# os20_newenc1.net
KiCad netlist of a schematic drawn in EAGLE
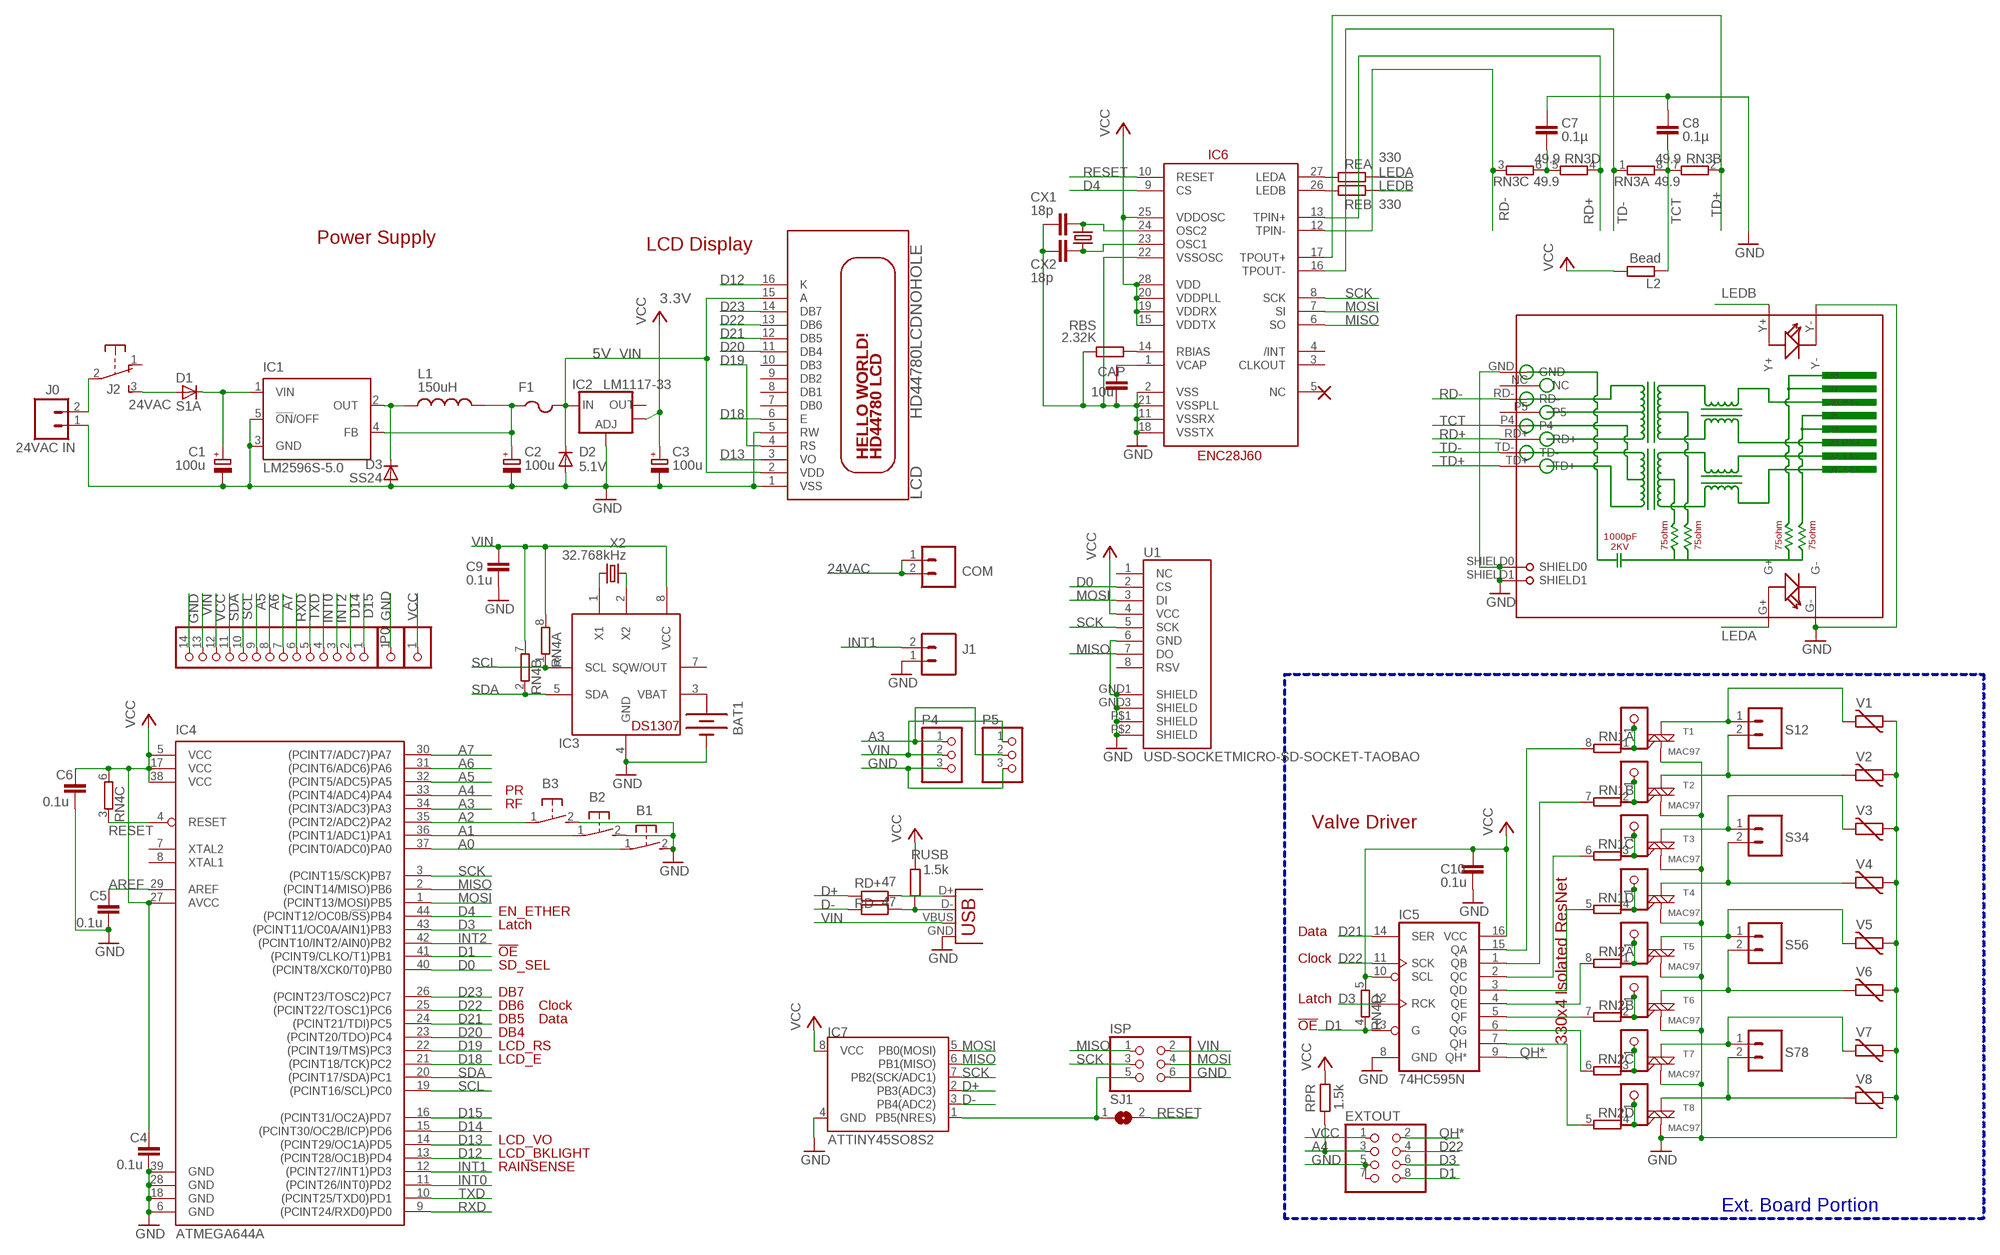
[diagram p0: schematic, sheet 1]

(export (version "E")
  (design (tool "Eeschema 10.0.6"))
  (components
    (comp (ref "B1")
      (value "31-XX")
      (footprint "eagle-import:B3F-31XX")
      (libsource (lib "eagle-import") (part "31-XX"))
    )
    (comp (ref "B2")
      (value "31-XX")
      (footprint "eagle-import:B3F-31XX")
      (libsource (lib "eagle-import") (part "31-XX"))
    )
    (comp (ref "B3")
      (value "31-XX")
      (footprint "eagle-import:B3F-31XX")
      (libsource (lib "eagle-import") (part "31-XX"))
    )
    (comp (ref "BAT1")
      (value "BATTERYBATTERY_12MM_SMT")
      (footprint "eagle-import:BATTCON_12MM_SMT")
      (libsource (lib "eagle-import") (part "BATTERYBATTERY_12MM_SMT"))
    )
    (comp (ref "C1")
      (value "100u")
      (footprint "eagle-import:E3,5-8")
      (libsource (lib "eagle-import") (part "CPOL-EUE3.5-8"))
    )
    (comp (ref "C2")
      (value "100u")
      (footprint "eagle-import:PANASONIC_D")
      (libsource (lib "eagle-import") (part "CPOL-EUD"))
    )
    (comp (ref "C3")
      (value "100u")
      (footprint "eagle-import:PANASONIC_D")
      (libsource (lib "eagle-import") (part "CPOL-EUD"))
    )
    (comp (ref "C4")
      (value "0.1u")
      (footprint "eagle-import:C0805")
      (libsource (lib "eagle-import") (part "C-EUC0805"))
    )
    (comp (ref "C5")
      (value "0.1u")
      (footprint "eagle-import:C0805")
      (libsource (lib "eagle-import") (part "C-EUC0805"))
    )
    (comp (ref "C6")
      (value "0.1u")
      (footprint "eagle-import:C0805")
      (libsource (lib "eagle-import") (part "C-EUC0805"))
    )
    (comp (ref "C7")
      (value "0.1µ")
      (footprint "eagle-import:C0805")
      (libsource (lib "eagle-import") (part "resistor_C-EUC0805"))
    )
    (comp (ref "C8")
      (value "0.1µ")
      (footprint "eagle-import:C0805")
      (libsource (lib "eagle-import") (part "resistor_C-EUC0805"))
    )
    (comp (ref "C9")
      (value "0.1u")
      (footprint "eagle-import:C0805")
      (libsource (lib "eagle-import") (part "C-EUC0805"))
    )
    (comp (ref "C10")
      (value "0.1u")
      (footprint "eagle-import:C0805")
      (libsource (lib "eagle-import") (part "C-EUC0805"))
    )
    (comp (ref "CAP")
      (value "10u")
      (footprint "eagle-import:C0805")
      (libsource (lib "eagle-import") (part "resistor_C-EUC0805"))
    )
    (comp (ref "COM")
      (value "M025MM")
      (footprint "eagle-import:SCREWTERMINAL-5MM-2")
      (libsource (lib "eagle-import") (part "M025MM"))
    )
    (comp (ref "CX1")
      (value "18p")
      (footprint "eagle-import:C0805")
      (libsource (lib "eagle-import") (part "resistor_C-EUC0805"))
    )
    (comp (ref "CX2")
      (value "18p")
      (footprint "eagle-import:C0805")
      (libsource (lib "eagle-import") (part "resistor_C-EUC0805"))
    )
    (comp (ref "D1")
      (value "S1A")
      (footprint "eagle-import:DO-214AC")
      (libsource (lib "eagle-import") (part "DIODE-DO-214AC"))
    )
    (comp (ref "D2")
      (value "5.1V")
      (footprint "eagle-import:MINIMELF")
      (libsource (lib "eagle-import") (part "DIODE-MINIMELF"))
    )
    (comp (ref "D3")
      (value "SS24")
      (footprint "eagle-import:DO-214AC")
      (libsource (lib "eagle-import") (part "DIODE-DO-214AC"))
    )
    (comp (ref "EXTOUT")
      (value "PINHD-2X4")
      (footprint "eagle-import:2X04")
      (libsource (lib "eagle-import") (part "PINHD-2X4"))
    )
    (comp (ref "F1")
      (value "PTCFUSE-1812")
      (footprint "eagle-import:1812")
      (libsource (lib "eagle-import") (part "PTCFUSE-1812"))
    )
    (comp (ref "IC1")
      (value "LM2596S-5.0")
      (footprint "eagle-import:TO263-5")
      (fields (field (name "MF") "NATIONAL SEMICONDUCTOR") (field (name "MPN") "LM2596S-ADJ/NOPB"))
      (libsource (lib "eagle-import") (part "LM2596S"))
    )
    (comp (ref "IC2")
      (value "LM1117-33")
      (footprint "eagle-import:SOT223")
      (libsource (lib "eagle-import") (part "V_REG_LM1117SOT223"))
    )
    (comp (ref "IC3")
      (value "DS1307")
      (footprint "eagle-import:SO08")
      (libsource (lib "eagle-import") (part "DS1307SOIC"))
    )
    (comp (ref "IC4")
      (value "ATMEGA644A")
      (footprint "eagle-import:TQFP44")
      (fields (field (name "MPN") "ATMEGA644PV-10AU"))
      (libsource (lib "eagle-import") (part "ATMEGA644A"))
    )
    (comp (ref "IC5")
      (value "74HC595N")
      (footprint "eagle-import:SO16")
      (libsource (lib "eagle-import") (part "74595DLS"))
    )
    (comp (ref "IC6")
      (value "ENC28J60")
      (footprint "eagle-import:SOIC28WLONG")
      (libsource (lib "eagle-import") (part "ENC28J60SO28LONG"))
    )
    (comp (ref "IC7")
      (value "ATTINY45SO8S2")
      (footprint "eagle-import:SO8S2")
      (libsource (lib "eagle-import") (part "ATTINY45SO8S2"))
    )
    (comp (ref "ISP")
      (value "PINHD-2X3")
      (footprint "eagle-import:2X03")
      (libsource (lib "eagle-import") (part "PINHD-2X3"))
    )
    (comp (ref "J0")
      (value "24VAC IN")
      (footprint "eagle-import:SCREWTERMINAL-5MM-2")
      (libsource (lib "eagle-import") (part "M025MM"))
    )
    (comp (ref "J1")
      (value "M025MM")
      (footprint "eagle-import:SCREWTERMINAL-5MM-2")
      (libsource (lib "eagle-import") (part "M025MM"))
    )
    (comp (ref "J2")
      (value "EG1206")
      (footprint "eagle-import:EG1206")
      (libsource (lib "eagle-import") (part "EG1206"))
    )
    (comp (ref "JP2")
      (value "PINHD-1X1CB")
      (footprint "eagle-import:1X01-CLEANBIG")
      (libsource (lib "eagle-import") (part "PINHD-1X1CB"))
    )
    (comp (ref "JP3")
      (value "PINHD-1X1CB")
      (footprint "eagle-import:1X01-CLEANBIG")
      (libsource (lib "eagle-import") (part "PINHD-1X1CB"))
    )
    (comp (ref "JP4")
      (value "PINHD-1X1CB")
      (footprint "eagle-import:1X01-CLEANBIG")
      (libsource (lib "eagle-import") (part "PINHD-1X1CB"))
    )
    (comp (ref "JP5")
      (value "PINHD-1X1CB")
      (footprint "eagle-import:1X01-CLEANBIG")
      (libsource (lib "eagle-import") (part "PINHD-1X1CB"))
    )
    (comp (ref "JP6")
      (value "PINHD-1X1CB")
      (footprint "eagle-import:1X01-CLEANBIG")
      (libsource (lib "eagle-import") (part "PINHD-1X1CB"))
    )
    (comp (ref "JP7")
      (value "PINHD-1X1CB")
      (footprint "eagle-import:1X01-CLEANBIG")
      (libsource (lib "eagle-import") (part "PINHD-1X1CB"))
    )
    (comp (ref "JP8")
      (value "PINHD-1X1CB")
      (footprint "eagle-import:1X01-CLEANBIG")
      (libsource (lib "eagle-import") (part "PINHD-1X1CB"))
    )
    (comp (ref "JP9")
      (value "PINHD-1X1CB")
      (footprint "eagle-import:1X01-CLEANBIG")
      (libsource (lib "eagle-import") (part "PINHD-1X1CB"))
    )
    (comp (ref "L1")
      (value "150uH")
      (footprint "eagle-import:CDRH125")
      (libsource (lib "eagle-import") (part "INDUCTORPWR"))
    )
    (comp (ref "L2")
      (value "Bead")
      (footprint "eagle-import:R0805")
      (libsource (lib "eagle-import") (part "R-EU_R0805"))
    )
    (comp (ref "LCD")
      (value "HD44780LCDNOHOLE")
      (footprint "eagle-import:LCD1602A")
      (libsource (lib "eagle-import") (part "HD44780LCDNOHOLE"))
    )
    (comp (ref "P0")
      (value "PINHD-1X14-CB")
      (footprint "eagle-import:1X14-CB")
      (libsource (lib "eagle-import") (part "PINHD-1X14-CB"))
    )
    (comp (ref "P1")
      (value "PINHD-1X1CB")
      (footprint "eagle-import:1X01-CLEANBIG")
      (libsource (lib "eagle-import") (part "PINHD-1X1CB"))
    )
    (comp (ref "P2")
      (value "PINHD-1X1CB")
      (footprint "eagle-import:1X01-CLEANBIG")
      (libsource (lib "eagle-import") (part "PINHD-1X1CB"))
    )
    (comp (ref "P4")
      (value "PINHD-1X3")
      (footprint "eagle-import:1X03")
      (libsource (lib "eagle-import") (part "PINHD-1X3"))
    )
    (comp (ref "P5")
      (value "PINHD-1X3")
      (footprint "eagle-import:1X03")
      (libsource (lib "eagle-import") (part "PINHD-1X3"))
    )
    (comp (ref "RBS")
      (value "2.32K")
      (footprint "eagle-import:R0805")
      (libsource (lib "eagle-import") (part "R-EU_R0805"))
    )
    (comp (ref "RD+")
      (value "47")
      (footprint "eagle-import:R0805")
      (libsource (lib "eagle-import") (part "R-EU_R0805"))
    )
    (comp (ref "RD-")
      (value "47")
      (footprint "eagle-import:R0805")
      (libsource (lib "eagle-import") (part "R-EU_R0805"))
    )
    (comp (ref "REA")
      (value "330")
      (footprint "eagle-import:R0805")
      (libsource (lib "eagle-import") (part "R-EU_R0805"))
    )
    (comp (ref "REB")
      (value "330")
      (footprint "eagle-import:R0805")
      (libsource (lib "eagle-import") (part "R-EU_R0805"))
    )
    (comp (ref "RJ45")
      (value "HR911105A")
      (footprint "eagle-import:HR911105A")
      (libsource (lib "eagle-import") (part "HR911105A"))
    )
    (comp (ref "RN1")
      (value "4R-NEXB38V")
      (footprint "eagle-import:EXB38V")
      (libsource (lib "eagle-import") (part "4R-NEXB38V"))
    )
    (comp (ref "RN2")
      (value "4R-NEXB38V")
      (footprint "eagle-import:EXB38V")
      (libsource (lib "eagle-import") (part "4R-NEXB38V"))
    )
    (comp (ref "RN3")
      (value "49.9")
      (footprint "eagle-import:EXB38V")
      (libsource (lib "eagle-import") (part "4R-NEXB38V"))
    )
    (comp (ref "RN4")
      (value "4R-NEXB38V")
      (footprint "eagle-import:EXB38V")
      (libsource (lib "eagle-import") (part "4R-NEXB38V"))
    )
    (comp (ref "RPR")
      (value "1.5k")
      (footprint "eagle-import:R0805")
      (libsource (lib "eagle-import") (part "R-EU_R0805"))
    )
    (comp (ref "RUSB")
      (value "1.5k")
      (footprint "eagle-import:R0805")
      (libsource (lib "eagle-import") (part "R-EU_R0805"))
    )
    (comp (ref "S12")
      (value "M025MM")
      (footprint "eagle-import:SCREWTERMINAL-5MM-2")
      (libsource (lib "eagle-import") (part "M025MM"))
    )
    (comp (ref "S34")
      (value "M025MM")
      (footprint "eagle-import:SCREWTERMINAL-5MM-2")
      (libsource (lib "eagle-import") (part "M025MM"))
    )
    (comp (ref "S56")
      (value "M025MM")
      (footprint "eagle-import:SCREWTERMINAL-5MM-2")
      (libsource (lib "eagle-import") (part "M025MM"))
    )
    (comp (ref "S78")
      (value "M025MM")
      (footprint "eagle-import:SCREWTERMINAL-5MM-2")
      (libsource (lib "eagle-import") (part "M025MM"))
    )
    (comp (ref "SJ1") (value "SJ") (footprint "eagle-import:SJ") (libsource (lib "eagle-import") (part "SJ")))
    (comp (ref "T1")
      (value "MAC97")
      (footprint "eagle-import:SOT223")
      (libsource (lib "eagle-import") (part "MAC97SOT223"))
    )
    (comp (ref "T2")
      (value "MAC97")
      (footprint "eagle-import:SOT223")
      (libsource (lib "eagle-import") (part "MAC97SOT223"))
    )
    (comp (ref "T3")
      (value "MAC97")
      (footprint "eagle-import:SOT223")
      (libsource (lib "eagle-import") (part "MAC97SOT223"))
    )
    (comp (ref "T4")
      (value "MAC97")
      (footprint "eagle-import:SOT223")
      (libsource (lib "eagle-import") (part "MAC97SOT223"))
    )
    (comp (ref "T5")
      (value "MAC97")
      (footprint "eagle-import:SOT223")
      (libsource (lib "eagle-import") (part "MAC97SOT223"))
    )
    (comp (ref "T6")
      (value "MAC97")
      (footprint "eagle-import:SOT223")
      (libsource (lib "eagle-import") (part "MAC97SOT223"))
    )
    (comp (ref "T7")
      (value "MAC97")
      (footprint "eagle-import:SOT223")
      (libsource (lib "eagle-import") (part "MAC97SOT223"))
    )
    (comp (ref "T8")
      (value "MAC97")
      (footprint "eagle-import:SOT223")
      (libsource (lib "eagle-import") (part "MAC97SOT223"))
    )
    (comp (ref "U1")
      (value "USD-SOCKETMICRO-SD-SOCKET-TAOBAO")
      (footprint "eagle-import:MICRO-SD-SOCKET-TAOBAO")
      (libsource (lib "eagle-import") (part "USD-SOCKETMICRO-SD-SOCKET-TAOBAO"))
    )
    (comp (ref "USB")
      (value "USBPTH")
      (footprint "eagle-import:USB-B-PTH")
      (libsource (lib "eagle-import") (part "USBPTH"))
    )
    (comp (ref "V1")
      (value "MOV")
      (footprint "eagle-import:R-5")
      (libsource (lib "eagle-import") (part "VARISTOR-5"))
    )
    (comp (ref "V2")
      (value "MOV")
      (footprint "eagle-import:R-5")
      (libsource (lib "eagle-import") (part "VARISTOR-5"))
    )
    (comp (ref "V3")
      (value "MOV")
      (footprint "eagle-import:R-5")
      (libsource (lib "eagle-import") (part "VARISTOR-5"))
    )
    (comp (ref "V4")
      (value "MOV")
      (footprint "eagle-import:R-5")
      (libsource (lib "eagle-import") (part "VARISTOR-5"))
    )
    (comp (ref "V5")
      (value "MOV")
      (footprint "eagle-import:R-5")
      (libsource (lib "eagle-import") (part "VARISTOR-5"))
    )
    (comp (ref "V6")
      (value "MOV")
      (footprint "eagle-import:R-5")
      (libsource (lib "eagle-import") (part "VARISTOR-5"))
    )
    (comp (ref "V7")
      (value "MOV")
      (footprint "eagle-import:R-5")
      (libsource (lib "eagle-import") (part "VARISTOR-5"))
    )
    (comp (ref "V8")
      (value "MOV")
      (footprint "eagle-import:R-5")
      (libsource (lib "eagle-import") (part "VARISTOR-5"))
    )
    (comp (ref "X1")
      (value "25MHz")
      (footprint "eagle-import:HC49US")
      (libsource (lib "eagle-import") (part "CRYSTALHC49US"))
    )
    (comp (ref "X2")
      (value "32.768kHz")
      (footprint "eagle-import:TC26H")
      (libsource (lib "eagle-import") (part "crystal_CRYSTALTC26H"))
    )
  )
  (nets
    (net (code "1") (name "/24VAC") (class "Default")
      (node (ref "COM") (pin "1") (pinfunction "1_1") (pintype "passive"))
      (node (ref "COM") (pin "2") (pinfunction "2_2") (pintype "passive"))
      (node (ref "D1") (pin "A") (pinfunction "A_A") (pintype "passive"))
      (node (ref "J2") (pin "3") (pinfunction "S_3") (pintype "passive"))
    )
    (net (code "2") (name "/A0") (class "Default")
      (node (ref "B1") (pin "1") (pinfunction "P_1") (pintype "passive"))
      (node (ref "IC4") (pin "37") (pinfunction "(PCINT0/ADC0)PA0_37") (pintype "bidirectional"))
    )
    (net (code "3") (name "/A1") (class "Default")
      (node (ref "B2") (pin "1") (pinfunction "P_1") (pintype "passive"))
      (node (ref "IC4") (pin "36") (pinfunction "(PCINT1/ADC1)PA1_36") (pintype "bidirectional"))
    )
    (net (code "4") (name "/A2") (class "Default")
      (node (ref "B3") (pin "1") (pinfunction "P_1") (pintype "passive"))
      (node (ref "IC4") (pin "35") (pinfunction "(PCINT2/ADC2)PA2_35") (pintype "bidirectional"))
    )
    (net (code "5") (name "/A3") (class "Default")
      (node (ref "IC4") (pin "34") (pinfunction "(PCINT3/ADC3)PA3_34") (pintype "bidirectional"))
      (node (ref "P4") (pin "1") (pinfunction "1_1") (pintype "passive"))
      (node (ref "P5") (pin "2") (pinfunction "2_2") (pintype "passive"))
    )
    (net (code "6") (name "/A4") (class "Default")
      (node (ref "EXTOUT") (pin "3") (pinfunction "3_3") (pintype "passive"))
      (node (ref "IC4") (pin "33") (pinfunction "(PCINT4/ADC4)PA4_33") (pintype "bidirectional"))
      (node (ref "RPR") (pin "1") (pinfunction "1_1") (pintype "passive"))
    )
    (net (code "7") (name "/A5") (class "Default")
      (node (ref "IC4") (pin "32") (pinfunction "(PCINT5/ADC5)PA5_32") (pintype "bidirectional"))
      (node (ref "P0") (pin "9") (pinfunction "9_9") (pintype "passive"))
    )
    (net (code "8") (name "/A6") (class "Default")
      (node (ref "IC4") (pin "31") (pinfunction "(PCINT6/ADC6)PA6_31") (pintype "bidirectional"))
      (node (ref "P0") (pin "8") (pinfunction "8_8") (pintype "passive"))
    )
    (net (code "9") (name "/A7") (class "Default")
      (node (ref "IC4") (pin "30") (pinfunction "(PCINT7/ADC7)PA7_30") (pintype "bidirectional"))
      (node (ref "P0") (pin "7") (pinfunction "7_7") (pintype "passive"))
    )
    (net (code "10") (name "/AREF") (class "Default")
      (node (ref "C5") (pin "1") (pinfunction "1_1") (pintype "passive"))
      (node (ref "IC4") (pin "29") (pinfunction "AREF_29") (pintype "passive"))
    )
    (net (code "11") (name "/D+") (class "Default")
      (node (ref "IC7") (pin "2") (pinfunction "PB3(ADC3)_2") (pintype "bidirectional"))
      (node (ref "RD+") (pin "1") (pinfunction "1_1") (pintype "passive"))
    )
    (net (code "12") (name "/D-") (class "Default")
      (node (ref "IC7") (pin "3") (pinfunction "PB4(ADC2)_3") (pintype "bidirectional"))
      (node (ref "RD-") (pin "1") (pinfunction "1_1") (pintype "passive"))
    )
    (net (code "13") (name "/D0") (class "Default")
      (node (ref "IC4") (pin "40") (pinfunction "(PCINT8/XCK0/T0)PB0_40") (pintype "bidirectional"))
      (node (ref "U1") (pin "2") (pinfunction "CS_2") (pintype "bidirectional"))
    )
    (net (code "14") (name "/D1") (class "Default")
      (node (ref "EXTOUT") (pin "8") (pinfunction "8_8") (pintype "passive"))
      (node (ref "IC4") (pin "41") (pinfunction "(PCINT9/CLKO/T1)PB1_41") (pintype "bidirectional"))
      (node (ref "IC5") (pin "13") (pinfunction "G_13") (pintype "input"))
      (node (ref "RN4") (pin "4") (pinfunction "1_4") (pintype "passive"))
    )
    (net (code "15") (name "/D3") (class "Default")
      (node (ref "EXTOUT") (pin "6") (pinfunction "6_6") (pintype "passive"))
      (node (ref "IC4") (pin "43") (pinfunction "(PCINT11/OC0A/AIN1)PB3_43") (pintype "bidirectional"))
      (node (ref "IC5") (pin "12") (pinfunction "RCK_12") (pintype "input"))
    )
    (net (code "16") (name "/D4") (class "Default")
      (node (ref "IC4") (pin "44") (pinfunction "(PCINT12/OC0B/~{SS})PB4_44") (pintype "bidirectional"))
      (node (ref "IC6") (pin "9") (pinfunction "CS_9") (pintype "bidirectional"))
    )
    (net (code "17") (name "/D12") (class "Default")
      (node (ref "IC4") (pin "13") (pinfunction "(PCINT28/OC1B)PD4_13") (pintype "bidirectional"))
      (node (ref "LCD") (pin "16") (pinfunction "K_16") (pintype "input"))
    )
    (net (code "18") (name "/D13") (class "Default")
      (node (ref "IC4") (pin "14") (pinfunction "(PCINT29/OC1A)PD5_14") (pintype "bidirectional"))
      (node (ref "LCD") (pin "3") (pinfunction "VO_3") (pintype "input"))
    )
    (net (code "19") (name "/D14") (class "Default")
      (node (ref "IC4") (pin "15") (pinfunction "(PCINT30/OC2B/ICP)PD6_15") (pintype "bidirectional"))
      (node (ref "P0") (pin "2") (pinfunction "2_2") (pintype "passive"))
    )
    (net (code "20") (name "/D15") (class "Default")
      (node (ref "IC4") (pin "16") (pinfunction "(PCINT31/OC2A)PD7_16") (pintype "bidirectional"))
      (node (ref "P0") (pin "1") (pinfunction "1_1") (pintype "passive"))
    )
    (net (code "21") (name "/D18") (class "Default")
      (node (ref "IC4") (pin "21") (pinfunction "(PCINT18/TCK)PC2_21") (pintype "output"))
      (node (ref "LCD") (pin "6") (pinfunction "E_6") (pintype "input"))
    )
    (net (code "22") (name "/D19") (class "Default")
      (node (ref "IC4") (pin "22") (pinfunction "(PCINT19/TMS)PC3_22") (pintype "output"))
      (node (ref "LCD") (pin "4") (pinfunction "RS_4") (pintype "input"))
    )
    (net (code "23") (name "/D20") (class "Default")
      (node (ref "IC4") (pin "23") (pinfunction "(PCINT20/TDO)PC4_23") (pintype "output"))
      (node (ref "LCD") (pin "11") (pinfunction "DB4_11") (pintype "bidirectional"))
    )
    (net (code "24") (name "/D21") (class "Default")
      (node (ref "IC4") (pin "24") (pinfunction "(PCINT21/TDI)PC5_24") (pintype "output"))
      (node (ref "IC5") (pin "14") (pinfunction "SER_14") (pintype "input"))
      (node (ref "LCD") (pin "12") (pinfunction "DB5_12") (pintype "bidirectional"))
    )
    (net (code "25") (name "/D22") (class "Default")
      (node (ref "EXTOUT") (pin "4") (pinfunction "4_4") (pintype "passive"))
      (node (ref "IC4") (pin "25") (pinfunction "(PCINT22/TOSC1)PC6_25") (pintype "output"))
      (node (ref "IC5") (pin "11") (pinfunction "SCK_11") (pintype "input"))
      (node (ref "LCD") (pin "13") (pinfunction "DB6_13") (pintype "bidirectional"))
    )
    (net (code "26") (name "/D23") (class "Default")
      (node (ref "IC4") (pin "26") (pinfunction "(PCINT23/TOSC2)PC7_26") (pintype "output"))
      (node (ref "LCD") (pin "14") (pinfunction "DB7_14") (pintype "bidirectional"))
    )
    (net (code "27") (name "/INT0") (class "Default")
      (node (ref "IC4") (pin "11") (pinfunction "(PCINT26/INT0)PD2_11") (pintype "bidirectional"))
      (node (ref "P0") (pin "4") (pinfunction "4_4") (pintype "passive"))
    )
    (net (code "28") (name "/INT1") (class "Default")
      (node (ref "IC4") (pin "12") (pinfunction "(PCINT27/INT1)PD3_12") (pintype "bidirectional"))
      (node (ref "J1") (pin "2") (pinfunction "2_2") (pintype "passive"))
    )
    (net (code "29") (name "/INT2") (class "Default")
      (node (ref "IC4") (pin "42") (pinfunction "(PCINT10/INT2/AIN0)PB2_42") (pintype "bidirectional"))
      (node (ref "P0") (pin "3") (pinfunction "3_3") (pintype "passive"))
    )
    (net (code "30") (name "/LEDA") (class "Default")
      (node (ref "REA") (pin "2") (pinfunction "2_2") (pintype "passive"))
      (node (ref "RJ45") (pin "G+") (pinfunction "G+_G+") (pintype "bidirectional"))
    )
    (net (code "31") (name "/LEDB") (class "Default")
      (node (ref "REB") (pin "2") (pinfunction "2_2") (pintype "passive"))
      (node (ref "RJ45") (pin "Y+") (pinfunction "Y+_Y+") (pintype "bidirectional"))
    )
    (net (code "32") (name "/MISO") (class "Default")
      (node (ref "IC4") (pin "2") (pinfunction "(PCINT14/MISO)PB6_2") (pintype "bidirectional"))
      (node (ref "IC6") (pin "6") (pinfunction "SO_6") (pintype "bidirectional"))
      (node (ref "IC7") (pin "6") (pinfunction "PB1(MISO)_6") (pintype "bidirectional"))
      (node (ref "ISP") (pin "1") (pinfunction "1_1") (pintype "passive"))
      (node (ref "U1") (pin "7") (pinfunction "DO_7") (pintype "bidirectional"))
    )
    (net (code "33") (name "/MOSI") (class "Default")
      (node (ref "IC4") (pin "1") (pinfunction "(PCINT13/MOSI)PB5_1") (pintype "bidirectional"))
      (node (ref "IC6") (pin "7") (pinfunction "SI_7") (pintype "bidirectional"))
      (node (ref "IC7") (pin "5") (pinfunction "PB0(MOSI)_5") (pintype "bidirectional"))
      (node (ref "ISP") (pin "4") (pinfunction "4_4") (pintype "passive"))
      (node (ref "U1") (pin "3") (pinfunction "DI_3") (pintype "bidirectional"))
    )
    (net (code "34") (name "/QH*") (class "Default")
      (node (ref "EXTOUT") (pin "2") (pinfunction "2_2") (pintype "passive"))
      (node (ref "IC5") (pin "9") (pinfunction "QH*_9") (pintype "tri_state"))
    )
    (net (code "35") (name "/RD+") (class "Default")
      (node (ref "IC6") (pin "13") (pinfunction "TPIN+_13") (pintype "bidirectional"))
      (node (ref "RJ45") (pin "RD+") (pinfunction "RD+_RD+") (pintype "bidirectional"))
      (node (ref "RN3") (pin "4") (pinfunction "1_4") (pintype "passive"))
    )
    (net (code "36") (name "/RD-") (class "Default")
      (node (ref "IC6") (pin "12") (pinfunction "TPIN-_12") (pintype "bidirectional"))
      (node (ref "RJ45") (pin "RD-") (pinfunction "RD-_RD-") (pintype "bidirectional"))
      (node (ref "RN3") (pin "3") (pinfunction "1_3") (pintype "passive"))
    )
    (net (code "37") (name "/RESET") (class "Default")
      (node (ref "IC4") (pin "4") (pinfunction "RESET_4") (pintype "input"))
      (node (ref "IC6") (pin "10") (pinfunction "RESET_10") (pintype "bidirectional"))
      (node (ref "RN4") (pin "3") (pinfunction "1_3") (pintype "passive"))
      (node (ref "SJ1") (pin "2") (pinfunction "2_2") (pintype "passive"))
    )
    (net (code "38") (name "/RXD") (class "Default")
      (node (ref "IC4") (pin "9") (pinfunction "(PCINT24/RXD0)PD0_9") (pintype "bidirectional"))
      (node (ref "P0") (pin "6") (pinfunction "6_6") (pintype "passive"))
    )
    (net (code "39") (name "/SCK") (class "Default")
      (node (ref "IC4") (pin "3") (pinfunction "(PCINT15/SCK)PB7_3") (pintype "bidirectional"))
      (node (ref "IC6") (pin "8") (pinfunction "SCK_8") (pintype "bidirectional"))
      (node (ref "IC7") (pin "7") (pinfunction "PB2(SCK/ADC1)_7") (pintype "bidirectional"))
      (node (ref "ISP") (pin "3") (pinfunction "3_3") (pintype "passive"))
      (node (ref "U1") (pin "5") (pinfunction "SCK_5") (pintype "bidirectional"))
    )
    (net (code "40") (name "/SCL") (class "Default")
      (node (ref "IC3") (pin "6") (pinfunction "SCL_6") (pintype "bidirectional"))
      (node (ref "IC4") (pin "19") (pinfunction "(PCINT16/SCL)PC0_19") (pintype "output"))
      (node (ref "P0") (pin "10") (pinfunction "10_10") (pintype "passive"))
      (node (ref "RN4") (pin "1") (pinfunction "1_1") (pintype "passive"))
    )
    (net (code "41") (name "/SDA") (class "Default")
      (node (ref "IC3") (pin "5") (pinfunction "SDA_5") (pintype "bidirectional"))
      (node (ref "IC4") (pin "20") (pinfunction "(PCINT17/SDA)PC1_20") (pintype "output"))
      (node (ref "P0") (pin "11") (pinfunction "11_11") (pintype "passive"))
      (node (ref "RN4") (pin "2") (pinfunction "1_2") (pintype "passive"))
    )
    (net (code "42") (name "/TCT") (class "Default")
      (node (ref "C8") (pin "2") (pinfunction "2_2") (pintype "passive"))
      (node (ref "L2") (pin "1") (pinfunction "1_1") (pintype "passive"))
      (node (ref "RJ45") (pin "P4") (pinfunction "P4_P4") (pintype "bidirectional"))
      (node (ref "RN3") (pin "7") (pinfunction "2_7") (pintype "passive"))
      (node (ref "RN3") (pin "8") (pinfunction "2_8") (pintype "passive"))
    )
    (net (code "43") (name "/TD+") (class "Default")
      (node (ref "IC6") (pin "17") (pinfunction "TPOUT+_17") (pintype "bidirectional"))
      (node (ref "RJ45") (pin "TD+") (pinfunction "TD+_TD+") (pintype "bidirectional"))
      (node (ref "RN3") (pin "2") (pinfunction "1_2") (pintype "passive"))
    )
    (net (code "44") (name "/TD-") (class "Default")
      (node (ref "IC6") (pin "16") (pinfunction "TPOUT-_16") (pintype "bidirectional"))
      (node (ref "RJ45") (pin "TD-") (pinfunction "TD-_TD-") (pintype "bidirectional"))
      (node (ref "RN3") (pin "1") (pinfunction "1_1") (pintype "passive"))
    )
    (net (code "45") (name "/TXD") (class "Default")
      (node (ref "IC4") (pin "10") (pinfunction "(PCINT25/TXD0)PD1_10") (pintype "bidirectional"))
      (node (ref "P0") (pin "5") (pinfunction "5_5") (pintype "passive"))
    )
    (net (code "46") (name "/VIN") (class "Default")
      (node (ref "C9") (pin "1") (pinfunction "1_1") (pintype "passive"))
      (node (ref "D2") (pin "C") (pinfunction "C_C") (pintype "passive"))
      (node (ref "F1") (pin "2") (pinfunction "2_2") (pintype "passive"))
      (node (ref "IC2") (pin "3") (pinfunction "IN_3") (pintype "input"))
      (node (ref "IC3") (pin "8") (pinfunction "VCC_8") (pintype "power_in"))
      (node (ref "ISP") (pin "2") (pinfunction "2_2") (pintype "passive"))
      (node (ref "LCD") (pin "15") (pinfunction "A_15") (pintype "input"))
      (node (ref "LCD") (pin "2") (pinfunction "VDD_2") (pintype "power_in"))
      (node (ref "P0") (pin "13") (pinfunction "13_13") (pintype "passive"))
      (node (ref "P4") (pin "2") (pinfunction "2_2") (pintype "passive"))
      (node (ref "P5") (pin "1") (pinfunction "1_1") (pintype "passive"))
      (node (ref "RN4") (pin "7") (pinfunction "2_7") (pintype "passive"))
      (node (ref "RN4") (pin "8") (pinfunction "2_8") (pintype "passive"))
      (node (ref "USB") (pin "VBUS") (pinfunction "VBUS_VBUS") (pintype "bidirectional"))
    )
    (net (code "47") (name "GND") (class "Default")
      (node (ref "B1") (pin "2") (pinfunction "S_2") (pintype "passive"))
      (node (ref "B2") (pin "2") (pinfunction "S_2") (pintype "passive"))
      (node (ref "B3") (pin "2") (pinfunction "S_2") (pintype "passive"))
      (node (ref "BAT1") (pin "P$1") (pinfunction "-_P$1") (pintype "power_in"))
      (node (ref "C1") (pin "-") (pinfunction "-_-") (pintype "passive"))
      (node (ref "C10") (pin "2") (pinfunction "2_2") (pintype "passive"))
      (node (ref "C2") (pin "-") (pinfunction "-_-") (pintype "passive"))
      (node (ref "C3") (pin "-") (pinfunction "-_-") (pintype "passive"))
      (node (ref "C4") (pin "2") (pinfunction "2_2") (pintype "passive"))
      (node (ref "C5") (pin "2") (pinfunction "2_2") (pintype "passive"))
      (node (ref "C6") (pin "2") (pinfunction "2_2") (pintype "passive"))
      (node (ref "C7") (pin "1") (pinfunction "1_1") (pintype "passive"))
      (node (ref "C8") (pin "1") (pinfunction "1_1") (pintype "passive"))
      (node (ref "C9") (pin "2") (pinfunction "2_2") (pintype "passive"))
      (node (ref "CAP") (pin "2") (pinfunction "2_2") (pintype "passive"))
      (node (ref "CX1") (pin "2") (pinfunction "2_2") (pintype "passive"))
      (node (ref "CX2") (pin "2") (pinfunction "2_2") (pintype "passive"))
      (node (ref "D2") (pin "A") (pinfunction "A_A") (pintype "passive"))
      (node (ref "D3") (pin "A") (pinfunction "A_A") (pintype "passive"))
      (node (ref "EXTOUT") (pin "5") (pinfunction "5_5") (pintype "passive"))
      (node (ref "EXTOUT") (pin "7") (pinfunction "7_7") (pintype "passive"))
      (node (ref "IC1") (pin "3") (pinfunction "GND_3") (pintype "power_in"))
      (node (ref "IC1") (pin "5") (pinfunction "~{ON}/OFF_5") (pintype "input"))
      (node (ref "IC2") (pin "1") (pinfunction "ADJ_1") (pintype "input"))
      (node (ref "IC3") (pin "4") (pinfunction "GND_4") (pintype "power_in"))
      (node (ref "IC4") (pin "18") (pinfunction "GND_18") (pintype "power_in"))
      (node (ref "IC4") (pin "28") (pinfunction "GND_28") (pintype "power_in"))
      (node (ref "IC4") (pin "39") (pinfunction "GND_39") (pintype "power_in"))
      (node (ref "IC4") (pin "6") (pinfunction "GND_6") (pintype "power_in"))
      (node (ref "IC5") (pin "8") (pinfunction "GND_8") (pintype "power_in"))
      (node (ref "IC6") (pin "11") (pinfunction "VSSRX_11") (pintype "bidirectional"))
      (node (ref "IC6") (pin "18") (pinfunction "VSSTX_18") (pintype "bidirectional"))
      (node (ref "IC6") (pin "2") (pinfunction "VSS_2") (pintype "bidirectional"))
      (node (ref "IC6") (pin "21") (pinfunction "VSSPLL_21") (pintype "bidirectional"))
      (node (ref "IC6") (pin "22") (pinfunction "VSSOSC_22") (pintype "bidirectional"))
      (node (ref "IC7") (pin "4") (pinfunction "GND_4") (pintype "bidirectional"))
      (node (ref "ISP") (pin "6") (pinfunction "6_6") (pintype "passive"))
      (node (ref "J0") (pin "1") (pinfunction "1_1") (pintype "passive"))
      (node (ref "J1") (pin "1") (pinfunction "1_1") (pintype "passive"))
      (node (ref "LCD") (pin "1") (pinfunction "VSS_1") (pintype "power_in"))
      (node (ref "LCD") (pin "5") (pinfunction "RW_5") (pintype "input"))
      (node (ref "P0") (pin "14") (pinfunction "14_14") (pintype "passive"))
      (node (ref "P1") (pin "1") (pinfunction "1_1") (pintype "passive"))
      (node (ref "P4") (pin "3") (pinfunction "3_3") (pintype "passive"))
      (node (ref "P5") (pin "3") (pinfunction "3_3") (pintype "passive"))
      (node (ref "RBS") (pin "1") (pinfunction "1_1") (pintype "passive"))
      (node (ref "RJ45") (pin "G-") (pinfunction "G-_G-") (pintype "bidirectional"))
      (node (ref "RJ45") (pin "GND") (pinfunction "GND_GND") (pintype "bidirectional"))
      (node (ref "RJ45") (pin "SHIELD0") (pinfunction "SHIELD0_SHIELD0") (pintype "bidirectional"))
      (node (ref "RJ45") (pin "SHIELD1") (pinfunction "SHIELD1_SHIELD1") (pintype "bidirectional"))
      (node (ref "RJ45") (pin "Y-") (pinfunction "Y-_Y-") (pintype "bidirectional"))
      (node (ref "T1") (pin "1") (pinfunction "M1_1") (pintype "bidirectional"))
      (node (ref "T2") (pin "1") (pinfunction "M1_1") (pintype "bidirectional"))
      (node (ref "T3") (pin "1") (pinfunction "M1_1") (pintype "bidirectional"))
      (node (ref "T4") (pin "1") (pinfunction "M1_1") (pintype "bidirectional"))
      (node (ref "T5") (pin "1") (pinfunction "M1_1") (pintype "bidirectional"))
      (node (ref "T6") (pin "1") (pinfunction "M1_1") (pintype "bidirectional"))
      (node (ref "T7") (pin "1") (pinfunction "M1_1") (pintype "bidirectional"))
      (node (ref "T8") (pin "1") (pinfunction "M1_1") (pintype "bidirectional"))
      (node (ref "U1") (pin "6") (pinfunction "GND_6") (pintype "bidirectional"))
      (node (ref "U1") (pin "GND1") (pinfunction "SHIELD_GND1") (pintype "bidirectional"))
      (node (ref "U1") (pin "GND3") (pinfunction "SHIELD_GND3") (pintype "bidirectional"))
      (node (ref "U1") (pin "P$1") (pinfunction "SHIELD_P$1") (pintype "bidirectional"))
      (node (ref "U1") (pin "P$2") (pinfunction "SHIELD_P$2") (pintype "bidirectional"))
      (node (ref "USB") (pin "GND") (pinfunction "GND_GND") (pintype "bidirectional"))
      (node (ref "V1") (pin "1") (pinfunction "1_1") (pintype "passive"))
      (node (ref "V2") (pin "1") (pinfunction "1_1") (pintype "passive"))
      (node (ref "V3") (pin "1") (pinfunction "1_1") (pintype "passive"))
      (node (ref "V4") (pin "1") (pinfunction "1_1") (pintype "passive"))
      (node (ref "V5") (pin "1") (pinfunction "1_1") (pintype "passive"))
      (node (ref "V6") (pin "1") (pinfunction "1_1") (pintype "passive"))
      (node (ref "V7") (pin "1") (pinfunction "1_1") (pintype "passive"))
      (node (ref "V8") (pin "1") (pinfunction "1_1") (pintype "passive"))
    )
    (net (code "48") (name "Net-(BAT1-+)") (class "Default")
      (node (ref "BAT1") (pin "P$2") (pinfunction "+_P$2") (pintype "power_in"))
      (node (ref "IC3") (pin "3") (pinfunction "VBAT_3") (pintype "power_in"))
    )
    (net (code "49") (name "Net-(IC1-FB)") (class "Default")
      (node (ref "C2") (pin "+") (pinfunction "+_+") (pintype "passive"))
      (node (ref "F1") (pin "1") (pinfunction "1_1") (pintype "passive"))
      (node (ref "IC1") (pin "4") (pinfunction "FB_4") (pintype "input"))
      (node (ref "L1") (pin "2") (pinfunction "2_2") (pintype "passive"))
    )
    (net (code "50") (name "Net-(IC1-OUT)") (class "Default")
      (node (ref "D3") (pin "C") (pinfunction "C_C") (pintype "passive"))
      (node (ref "IC1") (pin "2") (pinfunction "OUT_2") (pintype "output"))
      (node (ref "L1") (pin "1") (pinfunction "1_1") (pintype "passive"))
    )
    (net (code "51") (name "Net-(IC1-VIN)") (class "Default")
      (node (ref "C1") (pin "+") (pinfunction "+_+") (pintype "passive"))
      (node (ref "D1") (pin "C") (pinfunction "C_C") (pintype "passive"))
      (node (ref "IC1") (pin "1") (pinfunction "VIN_1") (pintype "input"))
    )
    (net (code "52") (name "Net-(IC3-X1)") (class "Default")
      (node (ref "IC3") (pin "1") (pinfunction "X1_1") (pintype "passive"))
      (node (ref "X2") (pin "2") (pinfunction "2_2") (pintype "passive"))
    )
    (net (code "53") (name "Net-(IC3-X2)") (class "Default")
      (node (ref "IC3") (pin "2") (pinfunction "X2_2") (pintype "passive"))
      (node (ref "X2") (pin "1") (pinfunction "1_1") (pintype "passive"))
    )
    (net (code "54") (name "Net-(IC5-QA)") (class "Default")
      (node (ref "IC5") (pin "15") (pinfunction "QA_15") (pintype "tri_state"))
      (node (ref "RN1") (pin "8") (pinfunction "2_8") (pintype "passive"))
    )
    (net (code "55") (name "Net-(IC5-QB)") (class "Default")
      (node (ref "IC5") (pin "1") (pinfunction "QB_1") (pintype "tri_state"))
      (node (ref "RN1") (pin "7") (pinfunction "2_7") (pintype "passive"))
    )
    (net (code "56") (name "Net-(IC5-QC)") (class "Default")
      (node (ref "IC5") (pin "2") (pinfunction "QC_2") (pintype "tri_state"))
      (node (ref "RN1") (pin "6") (pinfunction "2_6") (pintype "passive"))
    )
    (net (code "57") (name "Net-(IC5-QD)") (class "Default")
      (node (ref "IC5") (pin "3") (pinfunction "QD_3") (pintype "tri_state"))
      (node (ref "RN1") (pin "5") (pinfunction "2_5") (pintype "passive"))
    )
    (net (code "58") (name "Net-(IC5-QE)") (class "Default")
      (node (ref "IC5") (pin "4") (pinfunction "QE_4") (pintype "tri_state"))
      (node (ref "RN2") (pin "8") (pinfunction "2_8") (pintype "passive"))
    )
    (net (code "59") (name "Net-(IC5-QF)") (class "Default")
      (node (ref "IC5") (pin "5") (pinfunction "QF_5") (pintype "tri_state"))
      (node (ref "RN2") (pin "7") (pinfunction "2_7") (pintype "passive"))
    )
    (net (code "60") (name "Net-(IC5-QG)") (class "Default")
      (node (ref "IC5") (pin "6") (pinfunction "QG_6") (pintype "tri_state"))
      (node (ref "RN2") (pin "6") (pinfunction "2_6") (pintype "passive"))
    )
    (net (code "61") (name "Net-(IC5-QH)") (class "Default")
      (node (ref "IC5") (pin "7") (pinfunction "QH_7") (pintype "tri_state"))
      (node (ref "RN2") (pin "5") (pinfunction "2_5") (pintype "passive"))
    )
    (net (code "62") (name "Net-(IC6-LEDA)") (class "Default")
      (node (ref "IC6") (pin "27") (pinfunction "LEDA_27") (pintype "bidirectional"))
      (node (ref "REA") (pin "1") (pinfunction "1_1") (pintype "passive"))
    )
    (net (code "63") (name "Net-(IC6-LEDB)") (class "Default")
      (node (ref "IC6") (pin "26") (pinfunction "LEDB_26") (pintype "bidirectional"))
      (node (ref "REB") (pin "1") (pinfunction "1_1") (pintype "passive"))
    )
    (net (code "64") (name "Net-(IC6-OSC1)") (class "Default")
      (node (ref "CX2") (pin "1") (pinfunction "1_1") (pintype "passive"))
      (node (ref "IC6") (pin "23") (pinfunction "OSC1_23") (pintype "bidirectional"))
      (node (ref "X1") (pin "1") (pinfunction "1_1") (pintype "passive"))
    )
    (net (code "65") (name "Net-(IC6-OSC2)") (class "Default")
      (node (ref "CX1") (pin "1") (pinfunction "1_1") (pintype "passive"))
      (node (ref "IC6") (pin "24") (pinfunction "OSC2_24") (pintype "bidirectional"))
      (node (ref "X1") (pin "2") (pinfunction "2_2") (pintype "passive"))
    )
    (net (code "66") (name "Net-(IC6-RBIAS)") (class "Default")
      (node (ref "IC6") (pin "14") (pinfunction "RBIAS_14") (pintype "bidirectional"))
      (node (ref "RBS") (pin "2") (pinfunction "2_2") (pintype "passive"))
    )
    (net (code "67") (name "Net-(IC6-VCAP)") (class "Default")
      (node (ref "CAP") (pin "1") (pinfunction "1_1") (pintype "passive"))
      (node (ref "IC6") (pin "1") (pinfunction "VCAP_1") (pintype "bidirectional"))
    )
    (net (code "68") (name "Net-(IC7-PB5(NRES))") (class "Default")
      (node (ref "IC7") (pin "1") (pinfunction "PB5(NRES)_1") (pintype "bidirectional"))
      (node (ref "ISP") (pin "5") (pinfunction "5_5") (pintype "passive"))
      (node (ref "SJ1") (pin "1") (pinfunction "1_1") (pintype "passive"))
    )
    (net (code "69") (name "Net-(J2-P)") (class "Default")
      (node (ref "J0") (pin "2") (pinfunction "2_2") (pintype "passive"))
      (node (ref "J2") (pin "2") (pinfunction "P_2") (pintype "passive"))
    )
    (net (code "70") (name "Net-(RD+-Pad2)") (class "Default")
      (node (ref "RD+") (pin "2") (pinfunction "2_2") (pintype "passive"))
      (node (ref "USB") (pin "D+") (pinfunction "D+_D+") (pintype "bidirectional"))
    )
    (net (code "71") (name "Net-(RD--Pad2)") (class "Default")
      (node (ref "RD-") (pin "2") (pinfunction "2_2") (pintype "passive"))
      (node (ref "RUSB") (pin "1") (pinfunction "1_1") (pintype "passive"))
      (node (ref "USB") (pin "D-") (pinfunction "D-_D-") (pintype "bidirectional"))
    )
    (net (code "72") (name "Net-(RN1B-1)") (class "Default")
      (node (ref "JP3") (pin "1") (pinfunction "1_1") (pintype "passive"))
      (node (ref "RN1") (pin "2") (pinfunction "1_2") (pintype "passive"))
      (node (ref "T2") (pin "3") (pinfunction "G_3") (pintype "bidirectional"))
    )
    (net (code "73") (name "Net-(RN1C-1)") (class "Default")
      (node (ref "JP4") (pin "1") (pinfunction "1_1") (pintype "passive"))
      (node (ref "RN1") (pin "3") (pinfunction "1_3") (pintype "passive"))
      (node (ref "T3") (pin "3") (pinfunction "G_3") (pintype "bidirectional"))
    )
    (net (code "74") (name "Net-(RN1D-1)") (class "Default")
      (node (ref "JP5") (pin "1") (pinfunction "1_1") (pintype "passive"))
      (node (ref "RN1") (pin "4") (pinfunction "1_4") (pintype "passive"))
      (node (ref "T4") (pin "3") (pinfunction "G_3") (pintype "bidirectional"))
    )
    (net (code "75") (name "Net-(RN2B-1)") (class "Default")
      (node (ref "JP7") (pin "1") (pinfunction "1_1") (pintype "passive"))
      (node (ref "RN2") (pin "2") (pinfunction "1_2") (pintype "passive"))
      (node (ref "T6") (pin "3") (pinfunction "G_3") (pintype "bidirectional"))
    )
    (net (code "76") (name "Net-(RN2C-1)") (class "Default")
      (node (ref "JP8") (pin "1") (pinfunction "1_1") (pintype "passive"))
      (node (ref "RN2") (pin "3") (pinfunction "1_3") (pintype "passive"))
      (node (ref "T7") (pin "3") (pinfunction "G_3") (pintype "bidirectional"))
    )
    (net (code "77") (name "Net-(RN2D-1)") (class "Default")
      (node (ref "JP9") (pin "1") (pinfunction "1_1") (pintype "passive"))
      (node (ref "RN2") (pin "4") (pinfunction "1_4") (pintype "passive"))
      (node (ref "T8") (pin "3") (pinfunction "G_3") (pintype "bidirectional"))
    )
    (net (code "78") (name "Net-(RN3C-2)") (class "Default")
      (node (ref "C7") (pin "2") (pinfunction "2_2") (pintype "passive"))
      (node (ref "RN3") (pin "5") (pinfunction "2_5") (pintype "passive"))
      (node (ref "RN3") (pin "6") (pinfunction "2_6") (pintype "passive"))
    )
    (net (code "79") (name "Net-(T1-G)") (class "Default")
      (node (ref "JP2") (pin "1") (pinfunction "1_1") (pintype "passive"))
      (node (ref "RN1") (pin "1") (pinfunction "1_1") (pintype "passive"))
      (node (ref "T1") (pin "3") (pinfunction "G_3") (pintype "bidirectional"))
    )
    (net (code "80") (name "Net-(T1-M2)") (class "Default")
      (node (ref "S12") (pin "1") (pinfunction "1_1") (pintype "passive"))
      (node (ref "T1") (pin "4") (pinfunction "M2_4") (pintype "bidirectional"))
      (node (ref "V1") (pin "2") (pinfunction "2_2") (pintype "passive"))
    )
    (net (code "81") (name "Net-(T2-M2)") (class "Default")
      (node (ref "S12") (pin "2") (pinfunction "2_2") (pintype "passive"))
      (node (ref "T2") (pin "4") (pinfunction "M2_4") (pintype "bidirectional"))
      (node (ref "V2") (pin "2") (pinfunction "2_2") (pintype "passive"))
    )
    (net (code "82") (name "Net-(T3-M2)") (class "Default")
      (node (ref "S34") (pin "1") (pinfunction "1_1") (pintype "passive"))
      (node (ref "T3") (pin "4") (pinfunction "M2_4") (pintype "bidirectional"))
      (node (ref "V3") (pin "2") (pinfunction "2_2") (pintype "passive"))
    )
    (net (code "83") (name "Net-(T4-M2)") (class "Default")
      (node (ref "S34") (pin "2") (pinfunction "2_2") (pintype "passive"))
      (node (ref "T4") (pin "4") (pinfunction "M2_4") (pintype "bidirectional"))
      (node (ref "V4") (pin "2") (pinfunction "2_2") (pintype "passive"))
    )
    (net (code "84") (name "Net-(T5-G)") (class "Default")
      (node (ref "JP6") (pin "1") (pinfunction "1_1") (pintype "passive"))
      (node (ref "RN2") (pin "1") (pinfunction "1_1") (pintype "passive"))
      (node (ref "T5") (pin "3") (pinfunction "G_3") (pintype "bidirectional"))
    )
    (net (code "85") (name "Net-(T5-M2)") (class "Default")
      (node (ref "S56") (pin "1") (pinfunction "1_1") (pintype "passive"))
      (node (ref "T5") (pin "4") (pinfunction "M2_4") (pintype "bidirectional"))
      (node (ref "V5") (pin "2") (pinfunction "2_2") (pintype "passive"))
    )
    (net (code "86") (name "Net-(T6-M2)") (class "Default")
      (node (ref "S56") (pin "2") (pinfunction "2_2") (pintype "passive"))
      (node (ref "T6") (pin "4") (pinfunction "M2_4") (pintype "bidirectional"))
      (node (ref "V6") (pin "2") (pinfunction "2_2") (pintype "passive"))
    )
    (net (code "87") (name "Net-(T7-M2)") (class "Default")
      (node (ref "S78") (pin "1") (pinfunction "1_1") (pintype "passive"))
      (node (ref "T7") (pin "4") (pinfunction "M2_4") (pintype "bidirectional"))
      (node (ref "V7") (pin "2") (pinfunction "2_2") (pintype "passive"))
    )
    (net (code "88") (name "Net-(T8-M2)") (class "Default")
      (node (ref "S78") (pin "2") (pinfunction "2_2") (pintype "passive"))
      (node (ref "T8") (pin "4") (pinfunction "M2_4") (pintype "bidirectional"))
      (node (ref "V8") (pin "2") (pinfunction "2_2") (pintype "passive"))
    )
    (net (code "89") (name "VCC") (class "Default")
      (node (ref "C10") (pin "1") (pinfunction "1_1") (pintype "passive"))
      (node (ref "C3") (pin "+") (pinfunction "+_+") (pintype "passive"))
      (node (ref "C4") (pin "1") (pinfunction "1_1") (pintype "passive"))
      (node (ref "C6") (pin "1") (pinfunction "1_1") (pintype "passive"))
      (node (ref "EXTOUT") (pin "1") (pinfunction "1_1") (pintype "passive"))
      (node (ref "IC2") (pin "4") (pinfunction "OUT_4") (pintype "bidirectional"))
      (node (ref "IC4") (pin "17") (pinfunction "VCC_17") (pintype "power_in"))
      (node (ref "IC4") (pin "27") (pinfunction "AVCC_27") (pintype "power_in"))
      (node (ref "IC4") (pin "38") (pinfunction "VCC_38") (pintype "power_in"))
      (node (ref "IC4") (pin "5") (pinfunction "VCC_5") (pintype "power_in"))
      (node (ref "IC5") (pin "10") (pinfunction "SCL_10") (pintype "input"))
      (node (ref "IC5") (pin "16") (pinfunction "VCC_16") (pintype "power_in"))
      (node (ref "IC6") (pin "15") (pinfunction "VDDTX_15") (pintype "bidirectional"))
      (node (ref "IC6") (pin "19") (pinfunction "VDDRX_19") (pintype "bidirectional"))
      (node (ref "IC6") (pin "20") (pinfunction "VDDPLL_20") (pintype "bidirectional"))
      (node (ref "IC6") (pin "25") (pinfunction "VDDOSC_25") (pintype "bidirectional"))
      (node (ref "IC6") (pin "28") (pinfunction "VDD_28") (pintype "bidirectional"))
      (node (ref "IC7") (pin "8") (pinfunction "VCC_8") (pintype "bidirectional"))
      (node (ref "L2") (pin "2") (pinfunction "2_2") (pintype "passive"))
      (node (ref "P0") (pin "12") (pinfunction "12_12") (pintype "passive"))
      (node (ref "P2") (pin "1") (pinfunction "1_1") (pintype "passive"))
      (node (ref "RN4") (pin "5") (pinfunction "2_5") (pintype "passive"))
      (node (ref "RN4") (pin "6") (pinfunction "2_6") (pintype "passive"))
      (node (ref "RPR") (pin "2") (pinfunction "2_2") (pintype "passive"))
      (node (ref "RUSB") (pin "2") (pinfunction "2_2") (pintype "passive"))
      (node (ref "U1") (pin "4") (pinfunction "VCC_4") (pintype "bidirectional"))
    )
    (net (code "90") (name "unconnected-(IC2-OUT-Pad2)") (class "Default")
      (node (ref "IC2") (pin "2") (pinfunction "OUT_2") (pintype "bidirectional"))
    )
    (net (code "91") (name "unconnected-(IC3-SQW{slash}OUT-Pad7)") (class "Default")
      (node (ref "IC3") (pin "7") (pinfunction "SQW/OUT_7") (pintype "bidirectional"))
    )
    (net (code "92") (name "unconnected-(IC4-XTAL1-Pad8)") (class "Default")
      (node (ref "IC4") (pin "8") (pinfunction "XTAL1_8") (pintype "bidirectional"))
    )
    (net (code "93") (name "unconnected-(IC4-XTAL2-Pad7)") (class "Default")
      (node (ref "IC4") (pin "7") (pinfunction "XTAL2_7") (pintype "bidirectional"))
    )
    (net (code "94") (name "unconnected-(IC6-CLKOUT-Pad3)") (class "Default")
      (node (ref "IC6") (pin "3") (pinfunction "CLKOUT_3") (pintype "bidirectional"))
    )
    (net (code "95") (name "unconnected-(IC6-NC-Pad5)") (class "Default")
      (node (ref "IC6") (pin "5") (pinfunction "NC_5") (pintype "bidirectional"))
    )
    (net (code "96") (name "unconnected-(IC6-{slash}INT-Pad4)") (class "Default")
      (node (ref "IC6") (pin "4") (pinfunction "/INT_4") (pintype "bidirectional"))
    )
    (net (code "97") (name "unconnected-(J2-O-Pad1)") (class "Default")
      (node (ref "J2") (pin "1") (pinfunction "O_1") (pintype "passive"))
    )
    (net (code "98") (name "unconnected-(LCD-DB0-Pad7)") (class "Default")
      (node (ref "LCD") (pin "7") (pinfunction "DB0_7") (pintype "bidirectional"))
    )
    (net (code "99") (name "unconnected-(LCD-DB1-Pad8)") (class "Default")
      (node (ref "LCD") (pin "8") (pinfunction "DB1_8") (pintype "bidirectional"))
    )
    (net (code "100") (name "unconnected-(LCD-DB2-Pad9)") (class "Default")
      (node (ref "LCD") (pin "9") (pinfunction "DB2_9") (pintype "bidirectional"))
    )
    (net (code "101") (name "unconnected-(LCD-DB3-Pad10)") (class "Default")
      (node (ref "LCD") (pin "10") (pinfunction "DB3_10") (pintype "bidirectional"))
    )
    (net (code "102") (name "unconnected-(RJ45-PadNC)") (class "Default")
      (node (ref "RJ45") (pin "NC") (pinfunction "NC_NC") (pintype "bidirectional"))
    )
    (net (code "103") (name "unconnected-(RJ45-PadP5)") (class "Default")
      (node (ref "RJ45") (pin "P5") (pinfunction "P5_P5") (pintype "bidirectional"))
    )
    (net (code "104") (name "unconnected-(U1-NC-Pad1)") (class "Default")
      (node (ref "U1") (pin "1") (pinfunction "NC_1") (pintype "bidirectional"))
    )
    (net (code "105") (name "unconnected-(U1-RSV-Pad8)") (class "Default")
      (node (ref "U1") (pin "8") (pinfunction "RSV_8") (pintype "bidirectional"))
    )
  )
)
